# SparkFun_RTK_Facet_-_Main.net
KiCad netlist of a schematic drawn in EAGLE
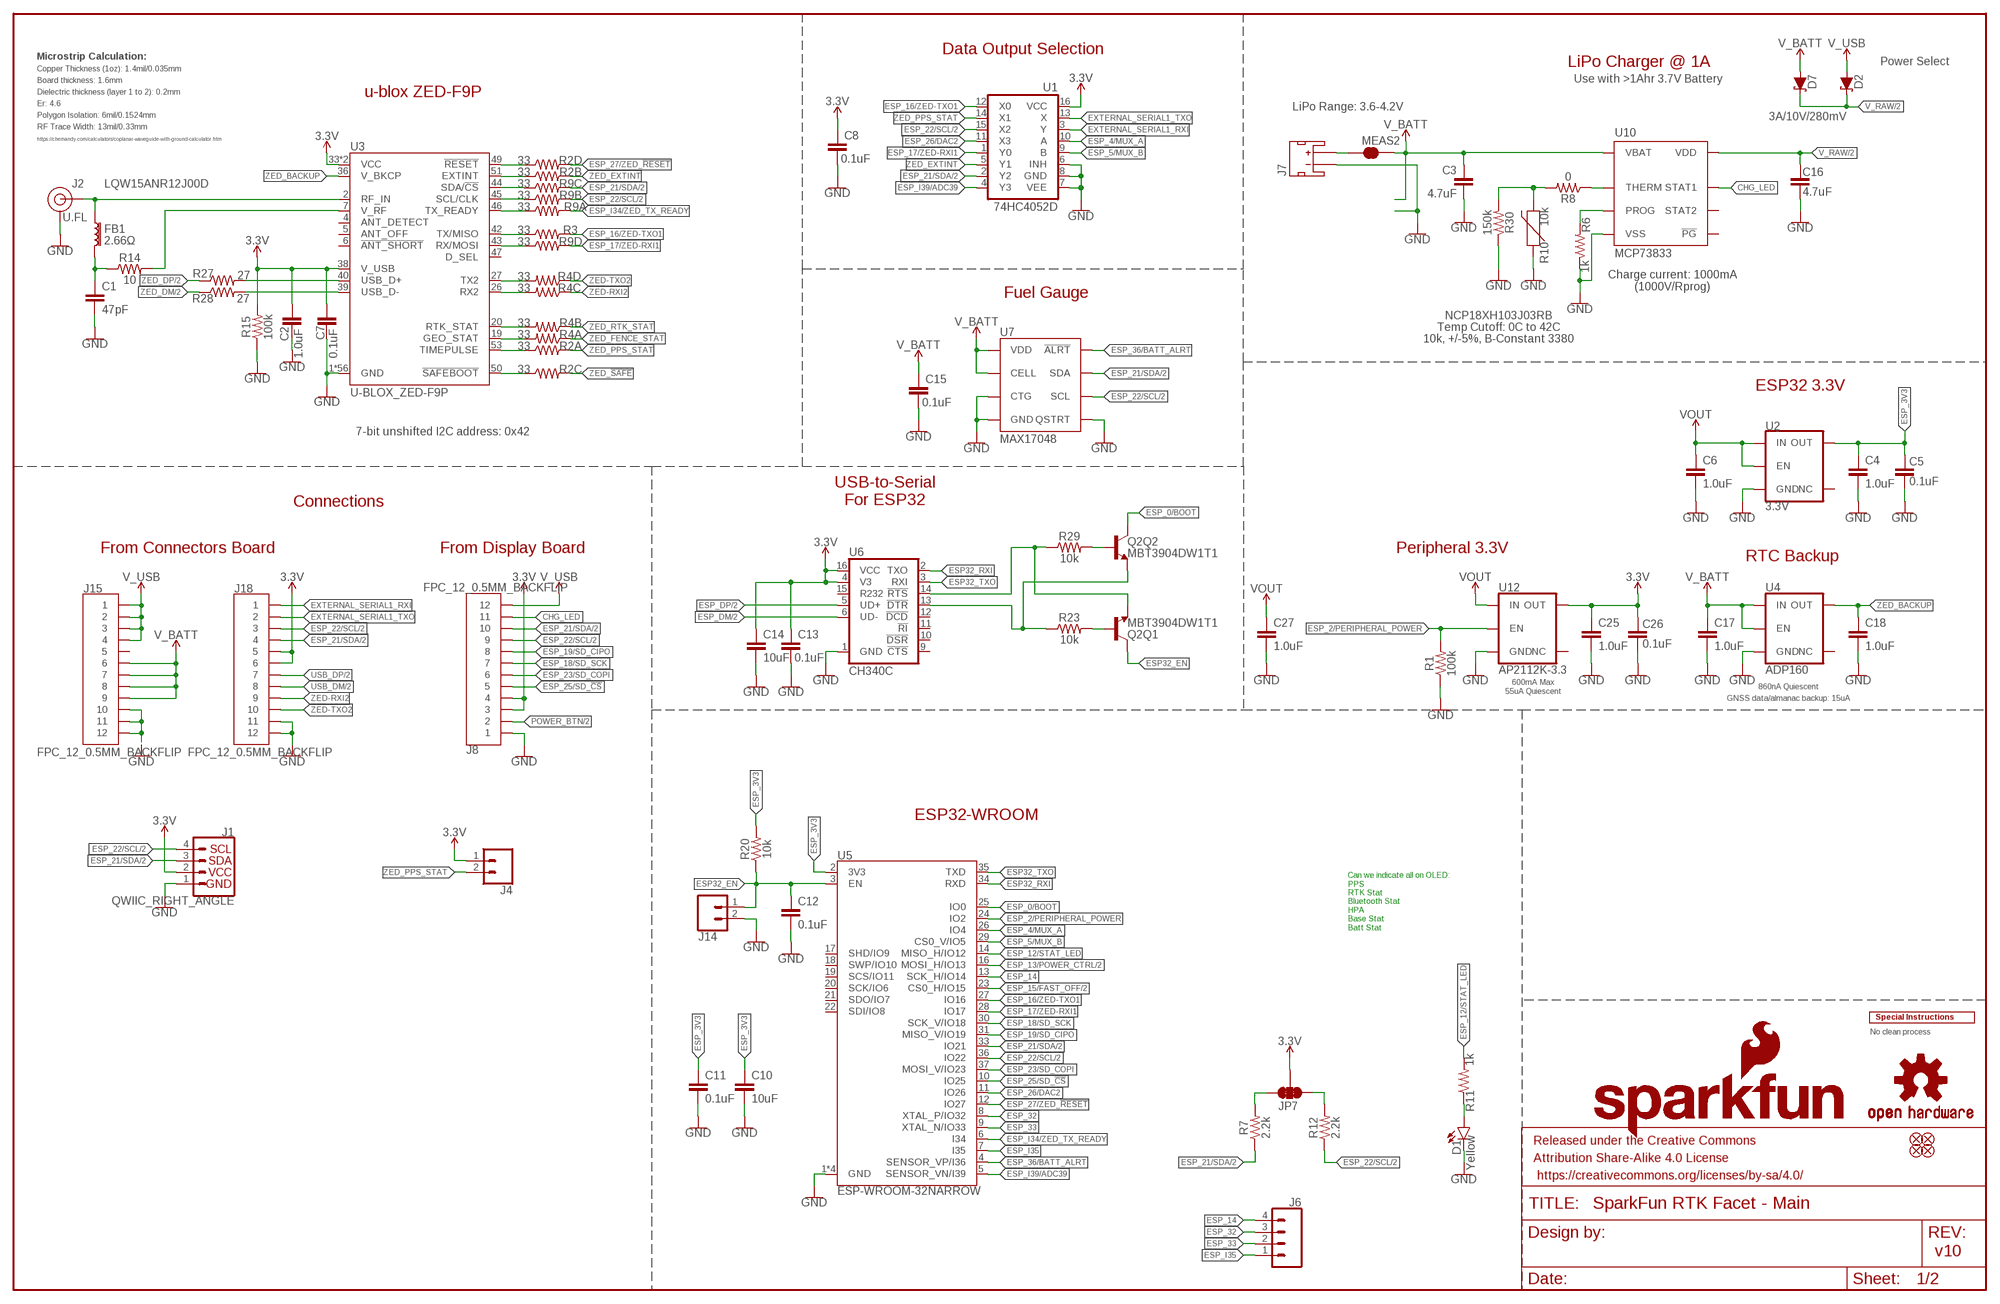
[diagram p0: schematic, sheet 1]
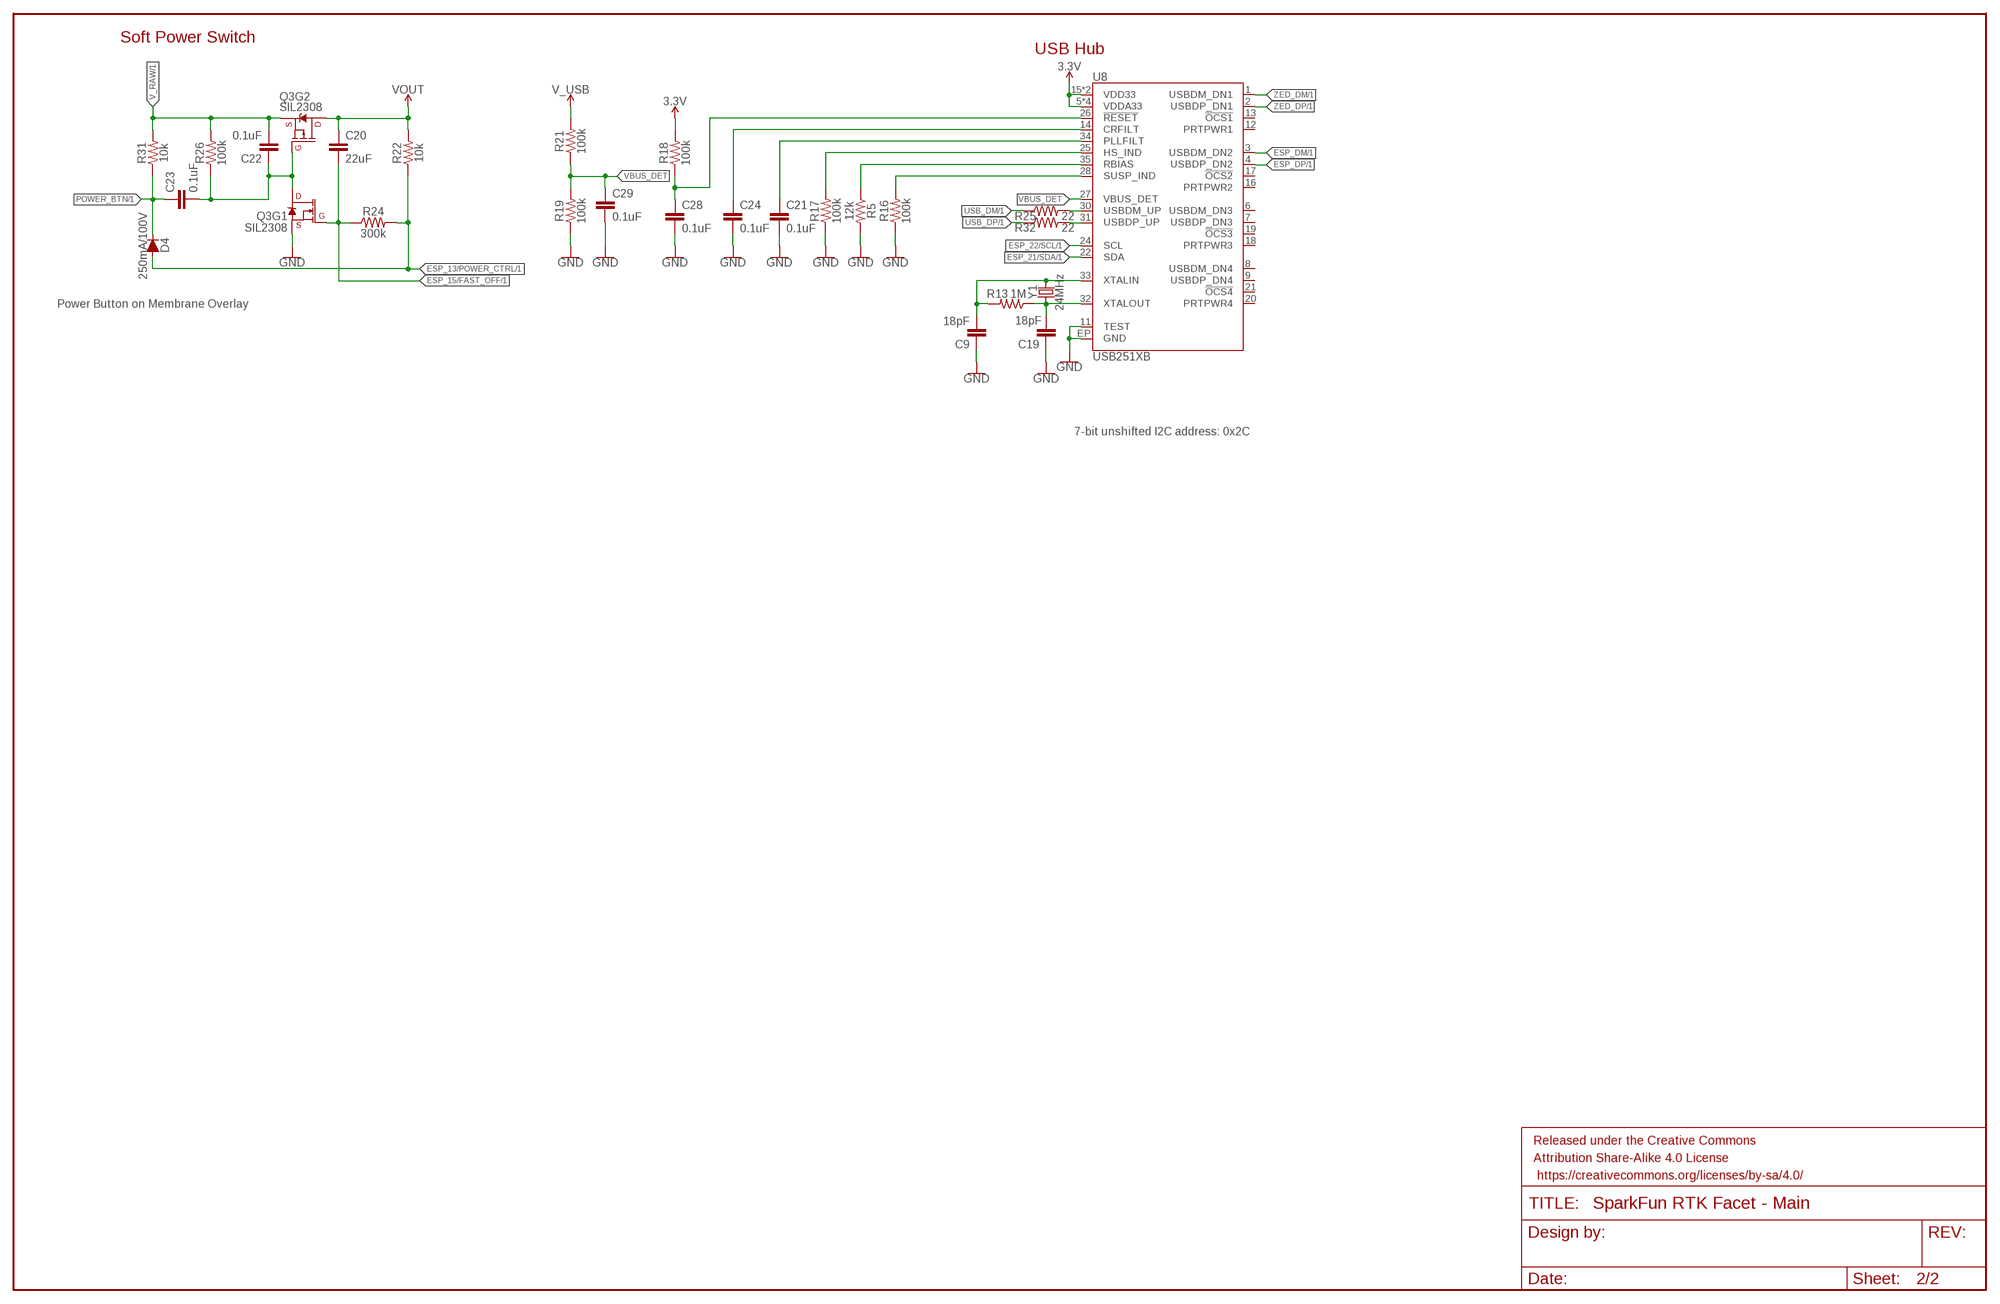
[diagram p1: schematic, sheet 2]

(export (version "E")
  (design (tool "Eeschema 10.0.6"))
  (components
    (comp (ref "C1")
      (value "47pF")
      (footprint "eagle-import:0402")
      (libsource (lib "eagle-import") (part "47PF-0402-25V-5%-X7R"))
    )
    (comp (ref "C2")
      (value "1.0uF")
      (footprint "eagle-import:0603")
      (libsource (lib "eagle-import") (part "1.0UF-0603-16V-10%-X7R"))
    )
    (comp (ref "C3")
      (value "4.7uF")
      (footprint "eagle-import:0603")
      (libsource (lib "eagle-import") (part "4.7UF-0603-35V-(20%)"))
    )
    (comp (ref "C4")
      (value "1.0uF")
      (footprint "eagle-import:0603")
      (libsource (lib "eagle-import") (part "1.0UF-0603-16V-10%-X7R"))
    )
    (comp (ref "C5")
      (value "0.1uF")
      (footprint "eagle-import:0603")
      (libsource (lib "eagle-import") (part "0.1UF-0603-25V-5%"))
    )
    (comp (ref "C6")
      (value "1.0uF")
      (footprint "eagle-import:0603")
      (libsource (lib "eagle-import") (part "1.0UF-0603-16V-10%-X7R"))
    )
    (comp (ref "C7")
      (value "0.1uF")
      (footprint "eagle-import:0603")
      (libsource (lib "eagle-import") (part "0.1UF-0603-25V-5%"))
    )
    (comp (ref "C8")
      (value "0.1uF")
      (footprint "eagle-import:0603")
      (libsource (lib "eagle-import") (part "0.1UF-0603-25V-(+80/-20%)"))
    )
    (comp (ref "C10")
      (value "10uF")
      (footprint "eagle-import:0603")
      (libsource (lib "eagle-import") (part "10UF-0603-6.3V-20%"))
    )
    (comp (ref "C11")
      (value "0.1uF")
      (footprint "eagle-import:0603")
      (libsource (lib "eagle-import") (part "0.1UF-0603-25V-(+80/-20%)"))
    )
    (comp (ref "C12")
      (value "0.1uF")
      (footprint "eagle-import:0603")
      (libsource (lib "eagle-import") (part "0.1UF-0603-25V-(+80/-20%)"))
    )
    (comp (ref "C13")
      (value "0.1uF")
      (footprint "eagle-import:0603")
      (libsource (lib "eagle-import") (part "0.1UF-0603-25V-(+80/-20%)"))
    )
    (comp (ref "C14")
      (value "10uF")
      (footprint "eagle-import:0603")
      (libsource (lib "eagle-import") (part "10UF-0603-6.3V-20%"))
    )
    (comp (ref "C15")
      (value "0.1uF")
      (footprint "eagle-import:0603")
      (libsource (lib "eagle-import") (part "0.1UF-0603-25V-(+80/-20%)"))
    )
    (comp (ref "C16")
      (value "4.7uF")
      (footprint "eagle-import:0603")
      (libsource (lib "eagle-import") (part "4.7UF-0603-35V-(20%)"))
    )
    (comp (ref "C17")
      (value "1.0uF")
      (footprint "eagle-import:0603")
      (libsource (lib "eagle-import") (part "1.0UF-0603-16V-10%-X7R"))
    )
    (comp (ref "C18")
      (value "1.0uF")
      (footprint "eagle-import:0603")
      (libsource (lib "eagle-import") (part "1.0UF-0603-16V-10%-X7R"))
    )
    (comp (ref "C25")
      (value "1.0uF")
      (footprint "eagle-import:0603")
      (libsource (lib "eagle-import") (part "1.0UF-0603-16V-10%-X7R"))
    )
    (comp (ref "C26")
      (value "0.1uF")
      (footprint "eagle-import:0603")
      (libsource (lib "eagle-import") (part "0.1UF-0603-25V-5%"))
    )
    (comp (ref "C27")
      (value "1.0uF")
      (footprint "eagle-import:0603")
      (libsource (lib "eagle-import") (part "1.0UF-0603-16V-10%-X7R"))
    )
    (comp (ref "D1")
      (value "Yellow")
      (footprint "eagle-import:LED-0603")
      (libsource (lib "eagle-import") (part "LED-YELLOW0603"))
    )
    (comp (ref "D2")
      (value "3A/10V/280mV")
      (footprint "eagle-import:SOD-323")
      (libsource (lib "eagle-import") (part "DIODE-SCHOTTKY-BAT60A"))
    )
    (comp (ref "D7")
      (value "3A/10V/280mV")
      (footprint "eagle-import:SOD-323")
      (libsource (lib "eagle-import") (part "DIODE-SCHOTTKY-BAT60A"))
    )
    (comp (ref "FB1")
      (value "2.66Ω")
      (footprint "eagle-import:0402-TIGHT")
      (libsource (lib "eagle-import") (part "FERRITE_BEAD-0402-2.66OHM-1GHZ"))
    )
    (comp (ref "FRAME2")
      (value "FRAME-LEDGER")
      (footprint "eagle-import:CREATIVE_COMMONS")
      (libsource (lib "eagle-import") (part "FRAME-LEDGER"))
    )
    (comp (ref "J1")
      (value "QWIIC_RIGHT_ANGLE")
      (footprint "eagle-import:JST04_1MM_RA")
      (libsource (lib "eagle-import") (part "QWIIC_CONNECTORJS-1MM"))
    )
    (comp (ref "J2")
      (value "U.FL")
      (footprint "eagle-import:U.FL")
      (libsource (lib "eagle-import") (part "U.FL2PIN"))
    )
    (comp (ref "J4")
      (value "CONN_021X02_NO_SILK")
      (footprint "eagle-import:1X02_NO_SILK")
      (libsource (lib "eagle-import") (part "CONN_021X02_NO_SILK"))
    )
    (comp (ref "J6")
      (value "CONN_041X04_NO_SILK_NO_POP")
      (footprint "eagle-import:1X04_NO_SILK")
      (libsource (lib "eagle-import") (part "CONN_041X04_NO_SILK_NO_POP"))
    )
    (comp (ref "J7")
      (value "JST_2MM_MALE")
      (footprint "eagle-import:JST-2-SMD")
      (libsource (lib "eagle-import") (part "JST_2MM_MALE"))
    )
    (comp (ref "J8")
      (value "FPC_12_0.5MM_BACKFLIP")
      (footprint "eagle-import:FPC_12_DOUBLESIDED_BACKFLIP")
      (libsource (lib "eagle-import") (part "FPC_12_0.5MM_BACKFLIP"))
    )
    (comp (ref "J14")
      (value "CONN_021X02_NO_SILK")
      (footprint "eagle-import:1X02_NO_SILK")
      (libsource (lib "eagle-import") (part "CONN_021X02_NO_SILK"))
    )
    (comp (ref "J15")
      (value "FPC_12_0.5MM_BACKFLIP")
      (footprint "eagle-import:FPC_12_DOUBLESIDED_BACKFLIP")
      (libsource (lib "eagle-import") (part "FPC_12_0.5MM_BACKFLIP"))
    )
    (comp (ref "J18")
      (value "FPC_12_0.5MM_BACKFLIP")
      (footprint "eagle-import:FPC_12_DOUBLESIDED_BACKFLIP")
      (libsource (lib "eagle-import") (part "FPC_12_0.5MM_BACKFLIP"))
    )
    (comp (ref "JP7")
      (value "JUMPER-SMT_3_2-NC_TRACE_SILK")
      (footprint "eagle-import:SMT-JUMPER_3_2-NC_TRACE_SILK")
      (libsource (lib "eagle-import") (part "JUMPER-SMT_3_2-NC_TRACE_SILK"))
    )
    (comp (ref "JP21")
      (value "FIDUCIALUFIDUCIAL")
      (footprint "eagle-import:FIDUCIAL-MICRO")
      (libsource (lib "eagle-import") (part "FIDUCIALUFIDUCIAL"))
    )
    (comp (ref "JP61")
      (value "FIDUCIALUFIDUCIAL")
      (footprint "eagle-import:FIDUCIAL-MICRO")
      (libsource (lib "eagle-import") (part "FIDUCIALUFIDUCIAL"))
    )
    (comp (ref "JP71")
      (value "FIDUCIALUFIDUCIAL")
      (footprint "eagle-import:FIDUCIAL-MICRO")
      (libsource (lib "eagle-import") (part "FIDUCIALUFIDUCIAL"))
    )
    (comp (ref "JP81")
      (value "FIDUCIALUFIDUCIAL")
      (footprint "eagle-import:FIDUCIAL-MICRO")
      (libsource (lib "eagle-import") (part "FIDUCIALUFIDUCIAL"))
    )
    (comp (ref "LOGO1")
      (value "OSHW-LOGOMINI")
      (footprint "eagle-import:OSHW-LOGO-MINI")
      (libsource (lib "eagle-import") (part "OSHW-LOGOMINI"))
    )
    (comp (ref "LOGO2")
      (value "SFE_LOGO_NAME_FLAME.1_INCH")
      (footprint "eagle-import:SFE_LOGO_NAME_FLAME_.1")
      (libsource (lib "eagle-import") (part "SFE_LOGO_NAME_FLAME.1_INCH"))
    )
    (comp (ref "MEAS2")
      (value "JUMPER-COMBO_2_NC_TRACE")
      (footprint "eagle-import:COMBO-JUMPER_2_NC_TRACE")
      (libsource (lib "eagle-import") (part "JUMPER-COMBO_2_NC_TRACE"))
    )
    (comp (ref "Q2")
      (value "MBT3904DW1T1")
      (footprint "eagle-import:SC70-6")
      (libsource (lib "eagle-import") (part "TRANS_NPN_DUAL-MBT3904DW1T1"))
    )
    (comp (ref "R1")
      (value "100k")
      (footprint "eagle-import:0603")
      (libsource (lib "eagle-import") (part "100KOHM-0603-1/10W-1%"))
    )
    (comp (ref "R2")
      (value "33")
      (footprint "eagle-import:1206_RA")
      (libsource (lib "eagle-import") (part "33OHM_RA-1206-1/16W-5%"))
    )
    (comp (ref "R3")
      (value "33")
      (footprint "eagle-import:0603")
      (libsource (lib "eagle-import") (part "33OHM-0603-1/10W-1%"))
    )
    (comp (ref "R4")
      (value "33")
      (footprint "eagle-import:1206_RA")
      (libsource (lib "eagle-import") (part "33OHM_RA-1206-1/16W-5%"))
    )
    (comp (ref "R6")
      (value "1k")
      (footprint "eagle-import:0603")
      (libsource (lib "eagle-import") (part "1KOHM-0603-1/10W-1%"))
    )
    (comp (ref "R7")
      (value "2.2k")
      (footprint "eagle-import:0603")
      (libsource (lib "eagle-import") (part "2.2KOHM-0603-1/10W-1%"))
    )
    (comp (ref "R8")
      (value "0")
      (footprint "eagle-import:0603")
      (libsource (lib "eagle-import") (part "0OHM-0603-1/10W"))
    )
    (comp (ref "R9")
      (value "33")
      (footprint "eagle-import:1206_RA")
      (libsource (lib "eagle-import") (part "33OHM_RA-1206-1/16W-5%"))
    )
    (comp (ref "R10")
      (value "10k")
      (footprint "eagle-import:0603")
      (libsource (lib "eagle-import") (part "NTC-THERMISTOR-0603"))
    )
    (comp (ref "R11")
      (value "1k")
      (footprint "eagle-import:0603")
      (libsource (lib "eagle-import") (part "1KOHM-0603-1/10W-1%"))
    )
    (comp (ref "R12")
      (value "2.2k")
      (footprint "eagle-import:0603")
      (libsource (lib "eagle-import") (part "2.2KOHM-0603-1/10W-1%"))
    )
    (comp (ref "R14")
      (value "10")
      (footprint "eagle-import:0603")
      (libsource (lib "eagle-import") (part "10OHM-0603-1/10W-1%"))
    )
    (comp (ref "R15")
      (value "100k")
      (footprint "eagle-import:0603")
      (libsource (lib "eagle-import") (part "100KOHM-0603-1/10W-1%"))
    )
    (comp (ref "R20")
      (value "10k")
      (footprint "eagle-import:0603")
      (libsource (lib "eagle-import") (part "10KOHM-0603-1/10W-1%"))
    )
    (comp (ref "R23")
      (value "10k")
      (footprint "eagle-import:0603")
      (libsource (lib "eagle-import") (part "10KOHM-0603-1/10W-1%"))
    )
    (comp (ref "R27")
      (value "27")
      (footprint "eagle-import:0603")
      (libsource (lib "eagle-import") (part "27OHM-0603-1/10W-1%"))
    )
    (comp (ref "R28")
      (value "27")
      (footprint "eagle-import:0603")
      (libsource (lib "eagle-import") (part "27OHM-0603-1/10W-1%"))
    )
    (comp (ref "R29")
      (value "10k")
      (footprint "eagle-import:0603")
      (libsource (lib "eagle-import") (part "10KOHM-0603-1/10W-1%"))
    )
    (comp (ref "R30")
      (value "150k")
      (footprint "eagle-import:0603")
      (libsource (lib "eagle-import") (part "150KOHM-0603-1/10W-1%"))
    )
    (comp (ref "U$2")
      (value "SPECIAL_INSTRUCTIONS-ORDERING")
      (footprint "eagle-import:ORDERING_INSTRUCTIONS")
      (libsource (lib "eagle-import") (part "SPECIAL_INSTRUCTIONS-ORDERING"))
    )
    (comp (ref "U1")
      (value "74HC4052D")
      (footprint "eagle-import:SO16")
      (libsource (lib "eagle-import") (part "744052DHC"))
    )
    (comp (ref "U2")
      (value "3.3V")
      (footprint "eagle-import:SOT23-5")
      (libsource (lib "eagle-import") (part "V_REG_AP2112K-3.3V"))
    )
    (comp (ref "U3")
      (value "U-BLOX_ZED-F9P")
      (footprint "eagle-import:ZED-F9P")
      (libsource (lib "eagle-import") (part "U-BLOX_ZED-F9P"))
    )
    (comp (ref "U4")
      (value "ADP160")
      (footprint "eagle-import:SOT23-5")
      (libsource (lib "eagle-import") (part "ADP160"))
    )
    (comp (ref "U5")
      (value "ESP-WROOM-32NARROW")
      (footprint "eagle-import:ESP-WROOM-32-NARROW")
      (libsource (lib "eagle-import") (part "ESP-WROOM-32NARROW"))
    )
    (comp (ref "U6")
      (value "CH340C")
      (footprint "eagle-import:SO016")
      (libsource (lib "eagle-import") (part "CH340C"))
    )
    (comp (ref "U7")
      (value "MAX17048")
      (footprint "eagle-import:DFN-8")
      (libsource (lib "eagle-import") (part "MAX17048DFN8"))
    )
    (comp (ref "U10")
      (value "MCP73833")
      (footprint "eagle-import:DFN-10")
      (libsource (lib "eagle-import") (part "MCP73833"))
    )
    (comp (ref "U12")
      (value "AP2112K-3.3")
      (footprint "eagle-import:SOT23-5")
      (libsource (lib "eagle-import") (part "V_REG_AP2112K-3.3V"))
    )
    (comp (ref "C9")
      (value "18pF")
      (footprint "eagle-import:0603")
      (libsource (lib "eagle-import") (part "18PF-0603-50V-5%"))
    )
    (comp (ref "C19")
      (value "18pF")
      (footprint "eagle-import:0603")
      (libsource (lib "eagle-import") (part "18PF-0603-50V-5%"))
    )
    (comp (ref "C20")
      (value "22uF")
      (footprint "eagle-import:0603")
      (libsource (lib "eagle-import") (part "22UF-0603-6.3V-20%"))
    )
    (comp (ref "C21")
      (value "0.1uF")
      (footprint "eagle-import:0603")
      (libsource (lib "eagle-import") (part "0.1UF-0603-25V-5%"))
    )
    (comp (ref "C22")
      (value "0.1uF")
      (footprint "eagle-import:0603")
      (libsource (lib "eagle-import") (part "0.1UF-0603-25V-5%"))
    )
    (comp (ref "C23")
      (value "0.1uF")
      (footprint "eagle-import:0603")
      (libsource (lib "eagle-import") (part "0.1UF-0603-25V-5%"))
    )
    (comp (ref "C24")
      (value "0.1uF")
      (footprint "eagle-import:0603")
      (libsource (lib "eagle-import") (part "0.1UF-0603-25V-5%"))
    )
    (comp (ref "C28")
      (value "0.1uF")
      (footprint "eagle-import:0603")
      (libsource (lib "eagle-import") (part "0.1UF-0603-25V-5%"))
    )
    (comp (ref "C29")
      (value "0.1uF")
      (footprint "eagle-import:0603")
      (libsource (lib "eagle-import") (part "0.1UF-0603-25V-5%"))
    )
    (comp (ref "D4")
      (value "250mA/100V")
      (footprint "eagle-import:SOD-323")
      (libsource (lib "eagle-import") (part "DIODE-BAS16J"))
    )
    (comp (ref "FRAME1")
      (value "FRAME-LEDGER")
      (footprint "eagle-import:CREATIVE_COMMONS")
      (libsource (lib "eagle-import") (part "FRAME-LEDGER"))
    )
    (comp (ref "Q3")
      (value "SIL2308")
      (footprint "eagle-import:SOT26")
      (libsource (lib "eagle-import") (part "MOSFET_COMPLIMENTARY_PAIR-SIL2308"))
    )
    (comp (ref "R5")
      (value "12k")
      (footprint "eagle-import:0603")
      (libsource (lib "eagle-import") (part "12KOHM-0603-1/10W-1%"))
    )
    (comp (ref "R13")
      (value "1M")
      (footprint "eagle-import:0603")
      (libsource (lib "eagle-import") (part "1MOHM-0603-1/4W-5%"))
    )
    (comp (ref "R16")
      (value "100k")
      (footprint "eagle-import:0603")
      (libsource (lib "eagle-import") (part "100KOHM-0603-1/10W-1%"))
    )
    (comp (ref "R17")
      (value "100k")
      (footprint "eagle-import:0603")
      (libsource (lib "eagle-import") (part "100KOHM-0603-1/10W-1%"))
    )
    (comp (ref "R18")
      (value "100k")
      (footprint "eagle-import:0603")
      (libsource (lib "eagle-import") (part "100KOHM-0603-1/10W-1%"))
    )
    (comp (ref "R19")
      (value "100k")
      (footprint "eagle-import:0603")
      (libsource (lib "eagle-import") (part "100KOHM-0603-1/10W-1%"))
    )
    (comp (ref "R21")
      (value "100k")
      (footprint "eagle-import:0603")
      (libsource (lib "eagle-import") (part "100KOHM-0603-1/10W-1%"))
    )
    (comp (ref "R22")
      (value "10k")
      (footprint "eagle-import:0603")
      (libsource (lib "eagle-import") (part "10KOHM-0603-1/10W-1%"))
    )
    (comp (ref "R24")
      (value "300k")
      (footprint "eagle-import:0603")
      (libsource (lib "eagle-import") (part "300KOHM-0603-1/10W-1%"))
    )
    (comp (ref "R25")
      (value "22")
      (footprint "eagle-import:0603")
      (libsource (lib "eagle-import") (part "22OHM-0603-1/10W-1%"))
    )
    (comp (ref "R26")
      (value "100k")
      (footprint "eagle-import:0603")
      (libsource (lib "eagle-import") (part "100KOHM-0603-1/10W-1%"))
    )
    (comp (ref "R31")
      (value "10k")
      (footprint "eagle-import:0603")
      (libsource (lib "eagle-import") (part "10KOHM-0603-1/10W-1%"))
    )
    (comp (ref "R32")
      (value "22")
      (footprint "eagle-import:0603")
      (libsource (lib "eagle-import") (part "22OHM-0603-1/10W-1%"))
    )
    (comp (ref "U8")
      (value "USB251XB")
      (footprint "eagle-import:QFN-36")
      (libsource (lib "eagle-import") (part "USB251XB"))
    )
    (comp (ref "Y1")
      (value "24MHz")
      (footprint "eagle-import:CRYSTAL-SMD-2.0X1.6MM")
      (libsource (lib "eagle-import") (part "CRYSTAL-24MHZ-SMD-2.0X1.6MM"))
    )
  )
  (nets
    (net (code "1") (name "3.3V") (class "Default")
      (node (ref "C13") (pin "1") (pinfunction "1_1") (pintype "passive"))
      (node (ref "C14") (pin "1") (pinfunction "1_1") (pintype "passive"))
      (node (ref "C2") (pin "1") (pinfunction "1_1") (pintype "passive"))
      (node (ref "C25") (pin "1") (pinfunction "1_1") (pintype "passive"))
      (node (ref "C26") (pin "2") (pinfunction "2_2") (pintype "passive"))
      (node (ref "C7") (pin "2") (pinfunction "2_2") (pintype "passive"))
      (node (ref "C8") (pin "1") (pinfunction "1_1") (pintype "passive"))
      (node (ref "J1") (pin "2") (pinfunction "2_2") (pintype "power_in"))
      (node (ref "J18") (pin "5") (pinfunction "5_5") (pintype "bidirectional"))
      (node (ref "J18") (pin "6") (pinfunction "6_6") (pintype "bidirectional"))
      (node (ref "J4") (pin "1") (pinfunction "1_1") (pintype "passive"))
      (node (ref "J8") (pin "3") (pinfunction "3_3") (pintype "bidirectional"))
      (node (ref "J8") (pin "4") (pinfunction "4_4") (pintype "bidirectional"))
      (node (ref "JP7") (pin "2") (pinfunction "2_2") (pintype "passive"))
      (node (ref "R15") (pin "2") (pinfunction "2_2") (pintype "passive"))
      (node (ref "R18") (pin "2") (pinfunction "2_2") (pintype "passive"))
      (node (ref "U1") (pin "16") (pinfunction "VCC_16") (pintype "power_in"))
      (node (ref "U12") (pin "5") (pinfunction "OUT_5") (pintype "passive"))
      (node (ref "U3") (pin "33") (pinfunction "VCC_33") (pintype "bidirectional"))
      (node (ref "U3") (pin "34") (pinfunction "VCC_34") (pintype "bidirectional"))
      (node (ref "U3") (pin "38") (pinfunction "V_USB_38") (pintype "bidirectional"))
      (node (ref "U6") (pin "16") (pinfunction "VCC_16") (pintype "bidirectional"))
      (node (ref "U6") (pin "4") (pinfunction "V3_4") (pintype "bidirectional"))
      (node (ref "U8") (pin "10") (pinfunction "VDDA33_10") (pintype "bidirectional"))
      (node (ref "U8") (pin "15") (pinfunction "VDD33_15") (pintype "bidirectional"))
      (node (ref "U8") (pin "23") (pinfunction "VDD33_23") (pintype "bidirectional"))
      (node (ref "U8") (pin "29") (pinfunction "VDDA33_29") (pintype "bidirectional"))
      (node (ref "U8") (pin "36") (pinfunction "VDDA33_36") (pintype "bidirectional"))
      (node (ref "U8") (pin "5") (pinfunction "VDDA33_5") (pintype "bidirectional"))
    )
    (net (code "2") (name "CHG_LED") (class "Default")
      (node (ref "J8") (pin "11") (pinfunction "11_11") (pintype "bidirectional"))
      (node (ref "U10") (pin "3") (pinfunction "STAT1_3") (pintype "bidirectional"))
    )
    (net (code "3") (name "ESP32_EN") (class "Default")
      (node (ref "C12") (pin "1") (pinfunction "1_1") (pintype "passive"))
      (node (ref "J14") (pin "1") (pinfunction "1_1") (pintype "passive"))
      (node (ref "Q2") (pin "3") (pinfunction "C_3") (pintype "passive"))
      (node (ref "R20") (pin "1") (pinfunction "1_1") (pintype "passive"))
      (node (ref "U5") (pin "3") (pinfunction "EN_3") (pintype "bidirectional"))
    )
    (net (code "4") (name "ESP32_RXI") (class "Default")
      (node (ref "U5") (pin "34") (pinfunction "RXD_34") (pintype "bidirectional"))
      (node (ref "U6") (pin "2") (pinfunction "TXO_2") (pintype "bidirectional"))
    )
    (net (code "5") (name "ESP32_TXO") (class "Default")
      (node (ref "U5") (pin "35") (pinfunction "TXD_35") (pintype "bidirectional"))
      (node (ref "U6") (pin "3") (pinfunction "RXI_3") (pintype "bidirectional"))
    )
    (net (code "6") (name "ESP_0{slash}BOOT") (class "Default")
      (node (ref "Q2") (pin "6") (pinfunction "C_6") (pintype "passive"))
      (node (ref "U5") (pin "25") (pinfunction "IO0_25") (pintype "bidirectional"))
    )
    (net (code "7") (name "ESP_2{slash}PERIPHERAL_POWER") (class "Default")
      (node (ref "R1") (pin "2") (pinfunction "2_2") (pintype "passive"))
      (node (ref "U12") (pin "3") (pinfunction "EN_3") (pintype "input"))
      (node (ref "U5") (pin "24") (pinfunction "IO2_24") (pintype "bidirectional"))
    )
    (net (code "8") (name "ESP_3V3") (class "Default")
      (node (ref "C10") (pin "1") (pinfunction "1_1") (pintype "passive"))
      (node (ref "C11") (pin "1") (pinfunction "1_1") (pintype "passive"))
      (node (ref "C4") (pin "1") (pinfunction "1_1") (pintype "passive"))
      (node (ref "C5") (pin "2") (pinfunction "2_2") (pintype "passive"))
      (node (ref "R20") (pin "2") (pinfunction "2_2") (pintype "passive"))
      (node (ref "U2") (pin "5") (pinfunction "OUT_5") (pintype "passive"))
      (node (ref "U5") (pin "2") (pinfunction "3V3_2") (pintype "bidirectional"))
    )
    (net (code "9") (name "ESP_4{slash}MUX_A") (class "Default")
      (node (ref "U1") (pin "10") (pinfunction "A_10") (pintype "input"))
      (node (ref "U5") (pin "26") (pinfunction "IO4_26") (pintype "bidirectional"))
    )
    (net (code "10") (name "ESP_5{slash}MUX_B") (class "Default")
      (node (ref "U1") (pin "9") (pinfunction "B_9") (pintype "input"))
      (node (ref "U5") (pin "29") (pinfunction "CS0_V/IO5_29") (pintype "bidirectional"))
    )
    (net (code "11") (name "ESP_12{slash}STAT_LED") (class "Default")
      (node (ref "R11") (pin "2") (pinfunction "2_2") (pintype "passive"))
      (node (ref "U5") (pin "14") (pinfunction "MISO_H/IO12_14") (pintype "bidirectional"))
    )
    (net (code "12") (name "ESP_13{slash}POWER_CTRL") (class "Default")
      (node (ref "D4") (pin "A") (pinfunction "A_A") (pintype "passive"))
      (node (ref "R22") (pin "1") (pinfunction "1_1") (pintype "passive"))
      (node (ref "R24") (pin "2") (pinfunction "2_2") (pintype "passive"))
      (node (ref "U5") (pin "16") (pinfunction "MOSI_H/IO13_16") (pintype "bidirectional"))
    )
    (net (code "13") (name "ESP_14") (class "Default")
      (node (ref "J6") (pin "4") (pinfunction "4_4") (pintype "passive"))
      (node (ref "U5") (pin "13") (pinfunction "SCK_H/IO14_13") (pintype "bidirectional"))
    )
    (net (code "14") (name "ESP_15{slash}FAST_OFF") (class "Default")
      (node (ref "C20") (pin "2") (pinfunction "2_2") (pintype "passive"))
      (node (ref "Q3") (pin "G1") (pinfunction "G_G1") (pintype "bidirectional"))
      (node (ref "R24") (pin "1") (pinfunction "1_1") (pintype "passive"))
      (node (ref "U5") (pin "23") (pinfunction "CS0_H/IO15_23") (pintype "bidirectional"))
    )
    (net (code "15") (name "ESP_16{slash}ZED-TXO1") (class "Default")
      (node (ref "R3") (pin "2") (pinfunction "2_2") (pintype "passive"))
      (node (ref "U1") (pin "12") (pinfunction "X0_12") (pintype "bidirectional"))
      (node (ref "U5") (pin "27") (pinfunction "IO16_27") (pintype "bidirectional"))
    )
    (net (code "16") (name "ESP_17{slash}ZED-RXI1") (class "Default")
      (node (ref "R9") (pin "P5") (pinfunction "2_P5") (pintype "passive"))
      (node (ref "U1") (pin "1") (pinfunction "Y0_1") (pintype "bidirectional"))
      (node (ref "U5") (pin "28") (pinfunction "IO17_28") (pintype "bidirectional"))
    )
    (net (code "17") (name "ESP_18{slash}SD_SCK") (class "Default")
      (node (ref "J8") (pin "7") (pinfunction "7_7") (pintype "bidirectional"))
      (node (ref "U5") (pin "30") (pinfunction "SCK_V/IO18_30") (pintype "bidirectional"))
    )
    (net (code "18") (name "ESP_19{slash}SD_CIPO") (class "Default")
      (node (ref "J8") (pin "8") (pinfunction "8_8") (pintype "bidirectional"))
      (node (ref "U5") (pin "31") (pinfunction "MISO_V/IO19_31") (pintype "bidirectional"))
    )
    (net (code "19") (name "ESP_21{slash}SDA") (class "Default")
      (node (ref "J1") (pin "3") (pinfunction "3_3") (pintype "passive"))
      (node (ref "J18") (pin "4") (pinfunction "4_4") (pintype "bidirectional"))
      (node (ref "J8") (pin "10") (pinfunction "10_10") (pintype "bidirectional"))
      (node (ref "R7") (pin "1") (pinfunction "1_1") (pintype "passive"))
      (node (ref "R9") (pin "P6") (pinfunction "2_P6") (pintype "passive"))
      (node (ref "U1") (pin "2") (pinfunction "Y2_2") (pintype "bidirectional"))
      (node (ref "U5") (pin "33") (pinfunction "IO21_33") (pintype "bidirectional"))
      (node (ref "U7") (pin "8") (pinfunction "SDA_8") (pintype "input"))
      (node (ref "U8") (pin "22") (pinfunction "SDA_22") (pintype "bidirectional"))
    )
    (net (code "20") (name "ESP_22{slash}SCL") (class "Default")
      (node (ref "J1") (pin "4") (pinfunction "4_4") (pintype "passive"))
      (node (ref "J18") (pin "3") (pinfunction "3_3") (pintype "bidirectional"))
      (node (ref "J8") (pin "9") (pinfunction "9_9") (pintype "bidirectional"))
      (node (ref "R12") (pin "1") (pinfunction "1_1") (pintype "passive"))
      (node (ref "R9") (pin "P7") (pinfunction "2_P7") (pintype "passive"))
      (node (ref "U1") (pin "15") (pinfunction "X2_15") (pintype "bidirectional"))
      (node (ref "U5") (pin "36") (pinfunction "IO22_36") (pintype "bidirectional"))
      (node (ref "U7") (pin "7") (pinfunction "SCL_7") (pintype "output"))
      (node (ref "U8") (pin "24") (pinfunction "SCL_24") (pintype "bidirectional"))
    )
    (net (code "21") (name "ESP_23{slash}SD_COPI") (class "Default")
      (node (ref "J8") (pin "6") (pinfunction "6_6") (pintype "bidirectional"))
      (node (ref "U5") (pin "37") (pinfunction "MOSI_V/IO23_37") (pintype "bidirectional"))
    )
    (net (code "22") (name "ESP_25{slash}SD_~{CS}") (class "Default")
      (node (ref "J8") (pin "5") (pinfunction "5_5") (pintype "bidirectional"))
      (node (ref "U5") (pin "10") (pinfunction "IO25_10") (pintype "bidirectional"))
    )
    (net (code "23") (name "ESP_26{slash}DAC2") (class "Default")
      (node (ref "U1") (pin "11") (pinfunction "X3_11") (pintype "bidirectional"))
      (node (ref "U5") (pin "11") (pinfunction "IO26_11") (pintype "bidirectional"))
    )
    (net (code "24") (name "ESP_27{slash}ZED_~{RESET}") (class "Default")
      (node (ref "R2") (pin "P5") (pinfunction "2_P5") (pintype "passive"))
      (node (ref "U5") (pin "12") (pinfunction "IO27_12") (pintype "bidirectional"))
    )
    (net (code "25") (name "ESP_32") (class "Default")
      (node (ref "J6") (pin "3") (pinfunction "3_3") (pintype "passive"))
      (node (ref "U5") (pin "8") (pinfunction "XTAL_P/IO32_8") (pintype "bidirectional"))
    )
    (net (code "26") (name "ESP_33") (class "Default")
      (node (ref "J6") (pin "2") (pinfunction "2_2") (pintype "passive"))
      (node (ref "U5") (pin "9") (pinfunction "XTAL_N/IO33_9") (pintype "bidirectional"))
    )
    (net (code "27") (name "ESP_36{slash}BATT_ALRT") (class "Default")
      (node (ref "U5") (pin "4") (pinfunction "SENSOR_VP/I36_4") (pintype "bidirectional"))
      (node (ref "U7") (pin "5") (pinfunction "~{ALRT}_5") (pintype "bidirectional"))
    )
    (net (code "28") (name "ESP_DM") (class "Default")
      (node (ref "U6") (pin "6") (pinfunction "UD-_6") (pintype "bidirectional"))
      (node (ref "U8") (pin "3") (pinfunction "USBDM_DN2_3") (pintype "bidirectional"))
    )
    (net (code "29") (name "ESP_DP") (class "Default")
      (node (ref "U6") (pin "5") (pinfunction "UD+_5") (pintype "bidirectional"))
      (node (ref "U8") (pin "4") (pinfunction "USBDP_DN2_4") (pintype "bidirectional"))
    )
    (net (code "30") (name "ESP_I34{slash}ZED_TX_READY") (class "Default")
      (node (ref "R9") (pin "P8") (pinfunction "2_P8") (pintype "passive"))
      (node (ref "U5") (pin "6") (pinfunction "I34_6") (pintype "bidirectional"))
    )
    (net (code "31") (name "ESP_I35") (class "Default")
      (node (ref "J6") (pin "1") (pinfunction "1_1") (pintype "passive"))
      (node (ref "U5") (pin "7") (pinfunction "I35_7") (pintype "bidirectional"))
    )
    (net (code "32") (name "ESP_I39{slash}ADC39") (class "Default")
      (node (ref "U1") (pin "4") (pinfunction "Y3_4") (pintype "bidirectional"))
      (node (ref "U5") (pin "5") (pinfunction "SENSOR_VN/I39_5") (pintype "bidirectional"))
    )
    (net (code "33") (name "EXTERNAL_SERIAL1_RXI") (class "Default")
      (node (ref "J18") (pin "1") (pinfunction "1_1") (pintype "bidirectional"))
      (node (ref "U1") (pin "3") (pinfunction "Y_3") (pintype "bidirectional"))
    )
    (net (code "34") (name "EXTERNAL_SERIAL1_TXO") (class "Default")
      (node (ref "J18") (pin "2") (pinfunction "2_2") (pintype "bidirectional"))
      (node (ref "U1") (pin "13") (pinfunction "X_13") (pintype "bidirectional"))
    )
    (net (code "35") (name "GND") (class "Default")
      (node (ref "C1") (pin "2") (pinfunction "2_2") (pintype "passive"))
      (node (ref "C10") (pin "2") (pinfunction "2_2") (pintype "passive"))
      (node (ref "C11") (pin "2") (pinfunction "2_2") (pintype "passive"))
      (node (ref "C12") (pin "2") (pinfunction "2_2") (pintype "passive"))
      (node (ref "C13") (pin "2") (pinfunction "2_2") (pintype "passive"))
      (node (ref "C14") (pin "2") (pinfunction "2_2") (pintype "passive"))
      (node (ref "C15") (pin "2") (pinfunction "2_2") (pintype "passive"))
      (node (ref "C16") (pin "2") (pinfunction "2_2") (pintype "passive"))
      (node (ref "C17") (pin "2") (pinfunction "2_2") (pintype "passive"))
      (node (ref "C18") (pin "2") (pinfunction "2_2") (pintype "passive"))
      (node (ref "C19") (pin "1") (pinfunction "1_1") (pintype "passive"))
      (node (ref "C2") (pin "2") (pinfunction "2_2") (pintype "passive"))
      (node (ref "C21") (pin "2") (pinfunction "2_2") (pintype "passive"))
      (node (ref "C24") (pin "2") (pinfunction "2_2") (pintype "passive"))
      (node (ref "C25") (pin "2") (pinfunction "2_2") (pintype "passive"))
      (node (ref "C26") (pin "1") (pinfunction "1_1") (pintype "passive"))
      (node (ref "C27") (pin "2") (pinfunction "2_2") (pintype "passive"))
      (node (ref "C28") (pin "2") (pinfunction "2_2") (pintype "passive"))
      (node (ref "C29") (pin "2") (pinfunction "2_2") (pintype "passive"))
      (node (ref "C3") (pin "2") (pinfunction "2_2") (pintype "passive"))
      (node (ref "C4") (pin "2") (pinfunction "2_2") (pintype "passive"))
      (node (ref "C5") (pin "1") (pinfunction "1_1") (pintype "passive"))
      (node (ref "C6") (pin "2") (pinfunction "2_2") (pintype "passive"))
      (node (ref "C7") (pin "1") (pinfunction "1_1") (pintype "passive"))
      (node (ref "C8") (pin "2") (pinfunction "2_2") (pintype "passive"))
      (node (ref "C9") (pin "1") (pinfunction "1_1") (pintype "passive"))
      (node (ref "D1") (pin "C") (pinfunction "C_C") (pintype "passive"))
      (node (ref "J1") (pin "1") (pinfunction "1_1") (pintype "power_in"))
      (node (ref "J14") (pin "2") (pinfunction "2_2") (pintype "passive"))
      (node (ref "J15") (pin "10") (pinfunction "10_10") (pintype "bidirectional"))
      (node (ref "J15") (pin "11") (pinfunction "11_11") (pintype "bidirectional"))
      (node (ref "J15") (pin "12") (pinfunction "12_12") (pintype "bidirectional"))
      (node (ref "J18") (pin "11") (pinfunction "11_11") (pintype "bidirectional"))
      (node (ref "J18") (pin "12") (pinfunction "12_12") (pintype "bidirectional"))
      (node (ref "J2") (pin "1") (pinfunction "GND_1") (pintype "bidirectional"))
      (node (ref "J2") (pin "2") (pinfunction "GND_2") (pintype "bidirectional"))
      (node (ref "J7") (pin "1") (pinfunction "-_1") (pintype "bidirectional"))
      (node (ref "J8") (pin "1") (pinfunction "1_1") (pintype "bidirectional"))
      (node (ref "Q3") (pin "S1") (pinfunction "S_S1") (pintype "bidirectional"))
      (node (ref "R1") (pin "1") (pinfunction "1_1") (pintype "passive"))
      (node (ref "R10") (pin "1") (pinfunction "1_1") (pintype "bidirectional"))
      (node (ref "R15") (pin "1") (pinfunction "1_1") (pintype "passive"))
      (node (ref "R16") (pin "1") (pinfunction "1_1") (pintype "passive"))
      (node (ref "R17") (pin "1") (pinfunction "1_1") (pintype "passive"))
      (node (ref "R19") (pin "1") (pinfunction "1_1") (pintype "passive"))
      (node (ref "R30") (pin "1") (pinfunction "1_1") (pintype "passive"))
      (node (ref "R5") (pin "2") (pinfunction "2_2") (pintype "passive"))
      (node (ref "R6") (pin "1") (pinfunction "1_1") (pintype "passive"))
      (node (ref "U1") (pin "6") (pinfunction "INH_6") (pintype "input"))
      (node (ref "U1") (pin "7") (pinfunction "VEE_7") (pintype "power_in"))
      (node (ref "U1") (pin "8") (pinfunction "GND_8") (pintype "power_in"))
      (node (ref "U10") (pin "11") (pinfunction "VSS_11") (pintype "bidirectional"))
      (node (ref "U10") (pin "5") (pinfunction "VSS_5") (pintype "bidirectional"))
      (node (ref "U12") (pin "2") (pinfunction "GND_2") (pintype "input"))
      (node (ref "U2") (pin "2") (pinfunction "GND_2") (pintype "input"))
      (node (ref "U3") (pin "1") (pinfunction "GND_1") (pintype "bidirectional"))
      (node (ref "U3") (pin "100") (pinfunction "GND_100") (pintype "bidirectional"))
      (node (ref "U3") (pin "101") (pinfunction "GND_101") (pintype "bidirectional"))
      (node (ref "U3") (pin "102") (pinfunction "GND_102") (pintype "bidirectional"))
      (node (ref "U3") (pin "12") (pinfunction "GND_12") (pintype "bidirectional"))
      (node (ref "U3") (pin "14") (pinfunction "GND_14") (pintype "bidirectional"))
      (node (ref "U3") (pin "3") (pinfunction "GND_3") (pintype "bidirectional"))
      (node (ref "U3") (pin "32") (pinfunction "GND_32") (pintype "bidirectional"))
      (node (ref "U3") (pin "37") (pinfunction "GND_37") (pintype "bidirectional"))
      (node (ref "U3") (pin "41") (pinfunction "GND_41") (pintype "bidirectional"))
      (node (ref "U3") (pin "48") (pinfunction "GND_48") (pintype "bidirectional"))
      (node (ref "U3") (pin "55") (pinfunction "GND_55") (pintype "bidirectional"))
      (node (ref "U3") (pin "56") (pinfunction "GND_56") (pintype "bidirectional"))
      (node (ref "U3") (pin "57") (pinfunction "GND_57") (pintype "bidirectional"))
      (node (ref "U3") (pin "58") (pinfunction "GND_58") (pintype "bidirectional"))
      (node (ref "U3") (pin "59") (pinfunction "GND_59") (pintype "bidirectional"))
      (node (ref "U3") (pin "60") (pinfunction "GND_60") (pintype "bidirectional"))
      (node (ref "U3") (pin "61") (pinfunction "GND_61") (pintype "bidirectional"))
      (node (ref "U3") (pin "62") (pinfunction "GND_62") (pintype "bidirectional"))
      (node (ref "U3") (pin "63") (pinfunction "GND_63") (pintype "bidirectional"))
      (node (ref "U3") (pin "64") (pinfunction "GND_64") (pintype "bidirectional"))
      (node (ref "U3") (pin "65") (pinfunction "GND_65") (pintype "bidirectional"))
      (node (ref "U3") (pin "66") (pinfunction "GND_66") (pintype "bidirectional"))
      (node (ref "U3") (pin "67") (pinfunction "GND_67") (pintype "bidirectional"))
      (node (ref "U3") (pin "68") (pinfunction "GND_68") (pintype "bidirectional"))
      (node (ref "U3") (pin "69") (pinfunction "GND_69") (pintype "bidirectional"))
      (node (ref "U3") (pin "70") (pinfunction "GND_70") (pintype "bidirectional"))
      (node (ref "U3") (pin "71") (pinfunction "GND_71") (pintype "bidirectional"))
      (node (ref "U3") (pin "72") (pinfunction "GND_72") (pintype "bidirectional"))
      (node (ref "U3") (pin "73") (pinfunction "GND_73") (pintype "bidirectional"))
      (node (ref "U3") (pin "74") (pinfunction "GND_74") (pintype "bidirectional"))
      (node (ref "U3") (pin "75") (pinfunction "GND_75") (pintype "bidirectional"))
      (node (ref "U3") (pin "76") (pinfunction "GND_76") (pintype "bidirectional"))
      (node (ref "U3") (pin "77") (pinfunction "GND_77") (pintype "bidirectional"))
      (node (ref "U3") (pin "78") (pinfunction "GND_78") (pintype "bidirectional"))
      (node (ref "U3") (pin "79") (pinfunction "GND_79") (pintype "bidirectional"))
      (node (ref "U3") (pin "80") (pinfunction "GND_80") (pintype "bidirectional"))
      (node (ref "U3") (pin "81") (pinfunction "GND_81") (pintype "bidirectional"))
      (node (ref "U3") (pin "82") (pinfunction "GND_82") (pintype "bidirectional"))
      (node (ref "U3") (pin "83") (pinfunction "GND_83") (pintype "bidirectional"))
      (node (ref "U3") (pin "84") (pinfunction "GND_84") (pintype "bidirectional"))
      (node (ref "U3") (pin "85") (pinfunction "GND_85") (pintype "bidirectional"))
      (node (ref "U3") (pin "86") (pinfunction "GND_86") (pintype "bidirectional"))
      (node (ref "U3") (pin "87") (pinfunction "GND_87") (pintype "bidirectional"))
      (node (ref "U3") (pin "88") (pinfunction "GND_88") (pintype "bidirectional"))
      (node (ref "U3") (pin "89") (pinfunction "GND_89") (pintype "bidirectional"))
      (node (ref "U3") (pin "90") (pinfunction "GND_90") (pintype "bidirectional"))
      (node (ref "U3") (pin "91") (pinfunction "GND_91") (pintype "bidirectional"))
      (node (ref "U3") (pin "92") (pinfunction "GND_92") (pintype "bidirectional"))
      (node (ref "U3") (pin "93") (pinfunction "GND_93") (pintype "bidirectional"))
      (node (ref "U3") (pin "94") (pinfunction "GND_94") (pintype "bidirectional"))
      (node (ref "U3") (pin "95") (pinfunction "GND_95") (pintype "bidirectional"))
      (node (ref "U3") (pin "96") (pinfunction "GND_96") (pintype "bidirectional"))
      (node (ref "U3") (pin "97") (pinfunction "GND_97") (pintype "bidirectional"))
      (node (ref "U3") (pin "98") (pinfunction "GND_98") (pintype "bidirectional"))
      (node (ref "U3") (pin "99") (pinfunction "GND_99") (pintype "bidirectional"))
      (node (ref "U4") (pin "2") (pinfunction "GND_2") (pintype "input"))
      (node (ref "U5") (pin "1") (pinfunction "GND_1") (pintype "bidirectional"))
      (node (ref "U5") (pin "15") (pinfunction "GND_15") (pintype "bidirectional"))
      (node (ref "U5") (pin "38") (pinfunction "GND_38") (pintype "bidirectional"))
      (node (ref "U5") (pin "GND") (pinfunction "GND_GND") (pintype "bidirectional"))
      (node (ref "U6") (pin "1") (pinfunction "GND_1") (pintype "bidirectional"))
      (node (ref "U7") (pin "1") (pinfunction "CTG_1") (pintype "input"))
      (node (ref "U7") (pin "4") (pinfunction "GND_4") (pintype "bidirectional"))
      (node (ref "U7") (pin "6") (pinfunction "QSTRT_6") (pintype "bidirectional"))
      (node (ref "U7") (pin "9") (pinfunction "GND_9") (pintype "bidirectional"))
      (node (ref "U8") (pin "11") (pinfunction "TEST_11") (pintype "bidirectional"))
      (node (ref "U8") (pin "EP") (pinfunction "GND_EP") (pintype "bidirectional"))
    )
    (net (code "36") (name "Net-(C1-Pad1)") (class "Default")
      (node (ref "C1") (pin "1") (pinfunction "1_1") (pintype "passive"))
      (node (ref "FB1") (pin "2") (pinfunction "2_2") (pintype "passive"))
      (node (ref "R14") (pin "1") (pinfunction "1_1") (pintype "passive"))
    )
    (net (code "37") (name "Net-(D1-PadA)") (class "Default")
      (node (ref "D1") (pin "A") (pinfunction "A_A") (pintype "passive"))
      (node (ref "R11") (pin "1") (pinfunction "1_1") (pintype "passive"))
    )
    (net (code "38") (name "Net-(J2-SIGNAL)") (class "Default")
      (node (ref "FB1") (pin "1") (pinfunction "1_1") (pintype "passive"))
      (node (ref "J2") (pin "FEED") (pinfunction "SIGNAL_FEED") (pintype "bidirectional"))
      (node (ref "U3") (pin "2") (pinfunction "RF_IN_2") (pintype "bidirectional"))
    )
    (net (code "39") (name "Net-(J7-+)") (class "Default")
      (node (ref "J7") (pin "2") (pinfunction "+_2") (pintype "bidirectional"))
      (node (ref "MEAS2") (pin "1") (pinfunction "1_1") (pintype "passive"))
      (node (ref "MEAS2") (pin "3") (pinfunction "1_3") (pintype "passive"))
    )
    (net (code "40") (name "Net-(JP7-Pad1)") (class "Default")
      (node (ref "JP7") (pin "1") (pinfunction "1_1") (pintype "passive"))
      (node (ref "R12") (pin "2") (pinfunction "2_2") (pintype "passive"))
    )
    (net (code "41") (name "Net-(JP7-Pad3)") (class "Default")
      (node (ref "JP7") (pin "3") (pinfunction "3_3") (pintype "passive"))
      (node (ref "R7") (pin "2") (pinfunction "2_2") (pintype "passive"))
    )
    (net (code "42") (name "Net-(Q2A-B)") (class "Default")
      (node (ref "Q2") (pin "5") (pinfunction "B_5") (pintype "passive"))
      (node (ref "R23") (pin "2") (pinfunction "2_2") (pintype "passive"))
    )
    (net (code "43") (name "Net-(Q2A-E)") (class "Default")
      (node (ref "Q2") (pin "4") (pinfunction "E_4") (pintype "passive"))
      (node (ref "R29") (pin "1") (pinfunction "1_1") (pintype "passive"))
      (node (ref "U6") (pin "14") (pinfunction "~{RTS}_14") (pintype "bidirectional"))
    )
    (net (code "44") (name "Net-(Q2B-B)") (class "Default")
      (node (ref "Q2") (pin "2") (pinfunction "B_2") (pintype "passive"))
      (node (ref "R29") (pin "2") (pinfunction "2_2") (pintype "passive"))
    )
    (net (code "45") (name "Net-(Q2B-E)") (class "Default")
      (node (ref "Q2") (pin "1") (pinfunction "E_1") (pintype "passive"))
      (node (ref "R23") (pin "1") (pinfunction "1_1") (pintype "passive"))
      (node (ref "U6") (pin "13") (pinfunction "~{DTR}_13") (pintype "bidirectional"))
    )
    (net (code "46") (name "Net-(Q3A-D)") (class "Default")
      (node (ref "C22") (pin "1") (pinfunction "1_1") (pintype "passive"))
      (node (ref "C23") (pin "2") (pinfunction "2_2") (pintype "passive"))
      (node (ref "Q3") (pin "D1") (pinfunction "D_D1") (pintype "bidirectional"))
      (node (ref "Q3") (pin "G2") (pinfunction "G_G2") (pintype "bidirectional"))
      (node (ref "R26") (pin "1") (pinfunction "1_1") (pintype "passive"))
    )
    (net (code "47") (name "Net-(R2A-1)") (class "Default")
      (node (ref "R2") (pin "P1") (pinfunction "1_P1") (pintype "passive"))
      (node (ref "U3") (pin "53") (pinfunction "TIMEPULSE_53") (pintype "bidirectional"))
    )
    (net (code "48") (name "Net-(R2B-1)") (class "Default")
      (node (ref "R2") (pin "P2") (pinfunction "1_P2") (pintype "passive"))
      (node (ref "U3") (pin "51") (pinfunction "EXTINT_51") (pintype "bidirectional"))
    )
    (net (code "49") (name "Net-(R2C-1)") (class "Default")
      (node (ref "R2") (pin "P3") (pinfunction "1_P3") (pintype "passive"))
      (node (ref "U3") (pin "50") (pinfunction "~{SAFEBOOT}_50") (pintype "bidirectional"))
    )
    (net (code "50") (name "Net-(R2D-1)") (class "Default")
      (node (ref "R2") (pin "P4") (pinfunction "1_P4") (pintype "passive"))
      (node (ref "U3") (pin "49") (pinfunction "~{RESET}_49") (pintype "bidirectional"))
    )
    (net (code "51") (name "Net-(R4A-2)") (class "Default")
      (node (ref "R4") (pin "P8") (pinfunction "2_P8") (pintype "passive"))
      (node (ref "U3") (pin "19") (pinfunction "GEO_STAT_19") (pintype "bidirectional"))
    )
    (net (code "52") (name "Net-(R4B-2)") (class "Default")
      (node (ref "R4") (pin "P7") (pinfunction "2_P7") (pintype "passive"))
      (node (ref "U3") (pin "20") (pinfunction "RTK_STAT_20") (pintype "bidirectional"))
    )
    (net (code "53") (name "Net-(R4C-2)") (class "Default")
      (node (ref "R4") (pin "P6") (pinfunction "2_P6") (pintype "passive"))
      (node (ref "U3") (pin "26") (pinfunction "RX2_26") (pintype "bidirectional"))
    )
    (net (code "54") (name "Net-(R4D-2)") (class "Default")
      (node (ref "R4") (pin "P5") (pinfunction "2_P5") (pintype "passive"))
      (node (ref "U3") (pin "27") (pinfunction "TX2_27") (pintype "bidirectional"))
    )
    (net (code "55") (name "Net-(R9A-1)") (class "Default")
      (node (ref "R9") (pin "P1") (pinfunction "1_P1") (pintype "passive"))
      (node (ref "U3") (pin "46") (pinfunction "TX_READY_46") (pintype "bidirectional"))
    )
    (net (code "56") (name "Net-(R9B-1)") (class "Default")
      (node (ref "R9") (pin "P2") (pinfunction "1_P2") (pintype "passive"))
      (node (ref "U3") (pin "45") (pinfunction "SCL/CLK_45") (pintype "bidirectional"))
    )
    (net (code "57") (name "Net-(R9C-1)") (class "Default")
      (node (ref "R9") (pin "P3") (pinfunction "1_P3") (pintype "passive"))
      (node (ref "U3") (pin "44") (pinfunction "SDA/~{CS}_44") (pintype "bidirectional"))
    )
    (net (code "58") (name "Net-(R9D-1)") (class "Default")
      (node (ref "R9") (pin "P4") (pinfunction "1_P4") (pintype "passive"))
      (node (ref "U3") (pin "43") (pinfunction "RX/MOSI_43") (pintype "bidirectional"))
    )
    (net (code "59") (name "Net-(R10-Pad2)") (class "Default")
      (node (ref "R10") (pin "2") (pinfunction "2_2") (pintype "bidirectional"))
      (node (ref "R30") (pin "2") (pinfunction "2_2") (pintype "passive"))
      (node (ref "R8") (pin "2") (pinfunction "2_2") (pintype "passive"))
    )
    (net (code "60") (name "Net-(U3-TX{slash}MISO)") (class "Default")
      (node (ref "R3") (pin "1") (pinfunction "1_1") (pintype "passive"))
      (node (ref "U3") (pin "42") (pinfunction "TX/MISO_42") (pintype "bidirectional"))
    )
    (net (code "61") (name "Net-(U3-USB_D+)") (class "Default")
      (node (ref "R27") (pin "2") (pinfunction "2_2") (pintype "passive"))
      (node (ref "U3") (pin "40") (pinfunction "USB_D+_40") (pintype "bidirectional"))
    )
    (net (code "62") (name "Net-(U3-USB_D-)") (class "Default")
      (node (ref "R28") (pin "2") (pinfunction "2_2") (pintype "passive"))
      (node (ref "U3") (pin "39") (pinfunction "USB_D-_39") (pintype "bidirectional"))
    )
    (net (code "63") (name "Net-(U3-V_RF)") (class "Default")
      (node (ref "R14") (pin "2") (pinfunction "2_2") (pintype "passive"))
      (node (ref "U3") (pin "7") (pinfunction "V_RF_7") (pintype "bidirectional"))
    )
    (net (code "64") (name "Net-(U8-CRFILT)") (class "Default")
      (node (ref "C24") (pin "1") (pinfunction "1_1") (pintype "passive"))
      (node (ref "U8") (pin "14") (pinfunction "CRFILT_14") (pintype "bidirectional"))
    )
    (net (code "65") (name "Net-(U8-HS_IND)") (class "Default")
      (node (ref "R17") (pin "2") (pinfunction "2_2") (pintype "passive"))
      (node (ref "U8") (pin "25") (pinfunction "HS_IND_25") (pintype "bidirectional"))
    )
    (net (code "66") (name "Net-(U8-PLLFILT)") (class "Default")
      (node (ref "C21") (pin "1") (pinfunction "1_1") (pintype "passive"))
      (node (ref "U8") (pin "34") (pinfunction "PLLFILT_34") (pintype "bidirectional"))
    )
    (net (code "67") (name "Net-(U8-RBIAS)") (class "Default")
      (node (ref "R5") (pin "1") (pinfunction "1_1") (pintype "passive"))
      (node (ref "U8") (pin "35") (pinfunction "RBIAS_35") (pintype "bidirectional"))
    )
    (net (code "68") (name "Net-(U8-SUSP_IND)") (class "Default")
      (node (ref "R16") (pin "2") (pinfunction "2_2") (pintype "passive"))
      (node (ref "U8") (pin "28") (pinfunction "SUSP_IND_28") (pintype "bidirectional"))
    )
    (net (code "69") (name "Net-(U8-USBDM_UP)") (class "Default")
      (node (ref "R25") (pin "2") (pinfunction "2_2") (pintype "passive"))
      (node (ref "U8") (pin "30") (pinfunction "USBDM_UP_30") (pintype "bidirectional"))
    )
    (net (code "70") (name "Net-(U8-USBDP_UP)") (class "Default")
      (node (ref "R32") (pin "2") (pinfunction "2_2") (pintype "passive"))
      (node (ref "U8") (pin "31") (pinfunction "USBDP_UP_31") (pintype "bidirectional"))
    )
    (net (code "71") (name "Net-(U8-XTALIN)") (class "Default")
      (node (ref "C9") (pin "2") (pinfunction "2_2") (pintype "passive"))
      (node (ref "R13") (pin "2") (pinfunction "2_2") (pintype "passive"))
      (node (ref "U8") (pin "33") (pinfunction "XTALIN_33") (pintype "bidirectional"))
      (node (ref "Y1") (pin "3") (pinfunction "2_3") (pintype "passive"))
    )
    (net (code "72") (name "Net-(U8-XTALOUT)") (class "Default")
      (node (ref "C19") (pin "2") (pinfunction "2_2") (pintype "passive"))
      (node (ref "R13") (pin "1") (pinfunction "1_1") (pintype "passive"))
      (node (ref "U8") (pin "32") (pinfunction "XTALOUT_32") (pintype "bidirectional"))
      (node (ref "Y1") (pin "1") (pinfunction "1_1") (pintype "passive"))
    )
    (net (code "73") (name "Net-(U8-~{RESET})") (class "Default")
      (node (ref "C28") (pin "1") (pinfunction "1_1") (pintype "passive"))
      (node (ref "R18") (pin "1") (pinfunction "1_1") (pintype "passive"))
      (node (ref "U8") (pin "26") (pinfunction "~{RESET}_26") (pintype "bidirectional"))
    )
    (net (code "74") (name "Net-(U10-PROG)") (class "Default")
      (node (ref "R6") (pin "2") (pinfunction "2_2") (pintype "passive"))
      (node (ref "U10") (pin "6") (pinfunction "PROG_6") (pintype "bidirectional"))
    )
    (net (code "75") (name "Net-(U10-THERM)") (class "Default")
      (node (ref "R8") (pin "1") (pinfunction "1_1") (pintype "passive"))
      (node (ref "U10") (pin "8") (pinfunction "THERM_8") (pintype "bidirectional"))
    )
    (net (code "76") (name "POWER_BTN") (class "Default")
      (node (ref "C23") (pin "1") (pinfunction "1_1") (pintype "passive"))
      (node (ref "D4") (pin "C") (pinfunction "C_C") (pintype "passive"))
      (node (ref "J8") (pin "2") (pinfunction "2_2") (pintype "bidirectional"))
      (node (ref "R31") (pin "1") (pinfunction "1_1") (pintype "passive"))
    )
    (net (code "77") (name "USB_DM") (class "Default")
      (node (ref "J18") (pin "8") (pinfunction "8_8") (pintype "bidirectional"))
      (node (ref "R25") (pin "1") (pinfunction "1_1") (pintype "passive"))
    )
    (net (code "78") (name "USB_DP") (class "Default")
      (node (ref "J18") (pin "7") (pinfunction "7_7") (pintype "bidirectional"))
      (node (ref "R32") (pin "1") (pinfunction "1_1") (pintype "passive"))
    )
    (net (code "79") (name "VBUS_DET") (class "Default")
      (node (ref "C29") (pin "1") (pinfunction "1_1") (pintype "passive"))
      (node (ref "R19") (pin "2") (pinfunction "2_2") (pintype "passive"))
      (node (ref "R21") (pin "1") (pinfunction "1_1") (pintype "passive"))
      (node (ref "U8") (pin "27") (pinfunction "VBUS_DET_27") (pintype "bidirectional"))
    )
    (net (code "80") (name "VOUT") (class "Default")
      (node (ref "C20") (pin "1") (pinfunction "1_1") (pintype "passive"))
      (node (ref "C27") (pin "1") (pinfunction "1_1") (pintype "passive"))
      (node (ref "C6") (pin "1") (pinfunction "1_1") (pintype "passive"))
      (node (ref "Q3") (pin "D2") (pinfunction "D_D2") (pintype "bidirectional"))
      (node (ref "R22") (pin "2") (pinfunction "2_2") (pintype "passive"))
      (node (ref "U12") (pin "1") (pinfunction "IN_1") (pintype "input"))
      (node (ref "U2") (pin "1") (pinfunction "IN_1") (pintype "input"))
      (node (ref "U2") (pin "3") (pinfunction "EN_3") (pintype "input"))
    )
    (net (code "81") (name "V_BATT") (class "Default")
      (node (ref "C15") (pin "1") (pinfunction "1_1") (pintype "passive"))
      (node (ref "C17") (pin "1") (pinfunction "1_1") (pintype "passive"))
      (node (ref "C3") (pin "1") (pinfunction "1_1") (pintype "passive"))
      (node (ref "D7") (pin "A") (pinfunction "A_A") (pintype "passive"))
      (node (ref "J15") (pin "6") (pinfunction "6_6") (pintype "bidirectional"))
      (node (ref "J15") (pin "7") (pinfunction "7_7") (pintype "bidirectional"))
      (node (ref "J15") (pin "8") (pinfunction "8_8") (pintype "bidirectional"))
      (node (ref "J15") (pin "9") (pinfunction "9_9") (pintype "bidirectional"))
      (node (ref "MEAS2") (pin "2") (pinfunction "2_2") (pintype "passive"))
      (node (ref "MEAS2") (pin "4") (pinfunction "2_4") (pintype "passive"))
      (node (ref "U10") (pin "10") (pinfunction "VBAT_10") (pintype "bidirectional"))
      (node (ref "U10") (pin "9") (pinfunction "VBAT_9") (pintype "bidirectional"))
      (node (ref "U4") (pin "1") (pinfunction "IN_1") (pintype "input"))
      (node (ref "U4") (pin "3") (pinfunction "EN_3") (pintype "input"))
      (node (ref "U7") (pin "2") (pinfunction "CELL_2") (pintype "input"))
      (node (ref "U7") (pin "3") (pinfunction "VDD_3") (pintype "bidirectional"))
    )
    (net (code "82") (name "V_RAW") (class "Default")
      (node (ref "C16") (pin "1") (pinfunction "1_1") (pintype "passive"))
      (node (ref "C22") (pin "2") (pinfunction "2_2") (pintype "passive"))
      (node (ref "D2") (pin "C") (pinfunction "C_C") (pintype "passive"))
      (node (ref "D7") (pin "C") (pinfunction "C_C") (pintype "passive"))
      (node (ref "Q3") (pin "S2") (pinfunction "S_S2") (pintype "bidirectional"))
      (node (ref "R26") (pin "2") (pinfunction "2_2") (pintype "passive"))
      (node (ref "R31") (pin "2") (pinfunction "2_2") (pintype "passive"))
      (node (ref "U10") (pin "1") (pinfunction "VDD_1") (pintype "bidirectional"))
      (node (ref "U10") (pin "2") (pinfunction "VDD_2") (pintype "bidirectional"))
    )
    (net (code "83") (name "V_USB") (class "Default")
      (node (ref "D2") (pin "A") (pinfunction "A_A") (pintype "passive"))
      (node (ref "J15") (pin "1") (pinfunction "1_1") (pintype "bidirectional"))
      (node (ref "J15") (pin "2") (pinfunction "2_2") (pintype "bidirectional"))
      (node (ref "J15") (pin "3") (pinfunction "3_3") (pintype "bidirectional"))
      (node (ref "J15") (pin "4") (pinfunction "4_4") (pintype "bidirectional"))
      (node (ref "J8") (pin "12") (pinfunction "12_12") (pintype "bidirectional"))
      (node (ref "R21") (pin "2") (pinfunction "2_2") (pintype "passive"))
    )
    (net (code "84") (name "ZED-RXI2") (class "Default")
      (node (ref "J18") (pin "9") (pinfunction "9_9") (pintype "bidirectional"))
      (node (ref "R4") (pin "P3") (pinfunction "1_P3") (pintype "passive"))
    )
    (net (code "85") (name "ZED-TXO2") (class "Default")
      (node (ref "J18") (pin "10") (pinfunction "10_10") (pintype "bidirectional"))
      (node (ref "R4") (pin "P4") (pinfunction "1_P4") (pintype "passive"))
    )
    (net (code "86") (name "ZED_BACKUP") (class "Default")
      (node (ref "C18") (pin "1") (pinfunction "1_1") (pintype "passive"))
      (node (ref "U3") (pin "36") (pinfunction "V_BKCP_36") (pintype "bidirectional"))
      (node (ref "U4") (pin "5") (pinfunction "OUT_5") (pintype "passive"))
    )
    (net (code "87") (name "ZED_DM") (class "Default")
      (node (ref "R28") (pin "1") (pinfunction "1_1") (pintype "passive"))
      (node (ref "U8") (pin "1") (pinfunction "USBDM_DN1_1") (pintype "bidirectional"))
    )
    (net (code "88") (name "ZED_DP") (class "Default")
      (node (ref "R27") (pin "1") (pinfunction "1_1") (pintype "passive"))
      (node (ref "U8") (pin "2") (pinfunction "USBDP_DN1_2") (pintype "bidirectional"))
    )
    (net (code "89") (name "ZED_EXTINT") (class "Default")
      (node (ref "R2") (pin "P7") (pinfunction "2_P7") (pintype "passive"))
      (node (ref "U1") (pin "5") (pinfunction "Y1_5") (pintype "bidirectional"))
    )
    (net (code "90") (name "ZED_FENCE_STAT") (class "Default")
      (node (ref "R4") (pin "P1") (pinfunction "1_P1") (pintype "passive"))
    )
    (net (code "91") (name "ZED_PPS_STAT") (class "Default")
      (node (ref "J4") (pin "2") (pinfunction "2_2") (pintype "passive"))
      (node (ref "R2") (pin "P8") (pinfunction "2_P8") (pintype "passive"))
      (node (ref "U1") (pin "14") (pinfunction "X1_14") (pintype "bidirectional"))
    )
    (net (code "92") (name "ZED_RTK_STAT") (class "Default")
      (node (ref "R4") (pin "P2") (pinfunction "1_P2") (pintype "passive"))
    )
    (net (code "93") (name "ZED_~{SAFE}") (class "Default")
      (node (ref "R2") (pin "P6") (pinfunction "2_P6") (pintype "passive"))
    )
    (net (code "94") (name "unconnected-(J7-PAD1-PadNC1)") (class "Default")
      (node (ref "J7") (pin "NC1") (pinfunction "PAD1_NC1") (pintype "bidirectional"))
    )
    (net (code "95") (name "unconnected-(J7-PAD2-PadNC2)") (class "Default")
      (node (ref "J7") (pin "NC2") (pinfunction "PAD2_NC2") (pintype "bidirectional"))
    )
    (net (code "96") (name "unconnected-(J15-Pad5)") (class "Default")
      (node (ref "J15") (pin "5") (pinfunction "5_5") (pintype "bidirectional"))
    )
    (net (code "97") (name "unconnected-(U2-NC-Pad4)") (class "Default")
      (node (ref "U2") (pin "4") (pinfunction "NC_4") (pintype "no_connect"))
    )
    (net (code "98") (name "unconnected-(U3-ANT_DETECT-Pad4)") (class "Default")
      (node (ref "U3") (pin "4") (pinfunction "ANT_DETECT_4") (pintype "bidirectional"))
    )
    (net (code "99") (name "unconnected-(U3-ANT_OFF-Pad5)") (class "Default")
      (node (ref "U3") (pin "5") (pinfunction "ANT_OFF_5") (pintype "bidirectional"))
    )
    (net (code "100") (name "unconnected-(U3-D_SEL-Pad47)") (class "Default")
      (node (ref "U3") (pin "47") (pinfunction "D_SEL_47") (pintype "bidirectional"))
    )
    (net (code "101") (name "unconnected-(U3-~{ANT_SHORT}-Pad6)") (class "Default")
      (node (ref "U3") (pin "6") (pinfunction "~{ANT_SHORT}_6") (pintype "bidirectional"))
    )
    (net (code "102") (name "unconnected-(U4-NC-Pad4)") (class "Default")
      (node (ref "U4") (pin "4") (pinfunction "NC_4") (pintype "no_connect"))
    )
    (net (code "103") (name "unconnected-(U5-SCK{slash}IO6-Pad20)") (class "Default")
      (node (ref "U5") (pin "20") (pinfunction "SCK/IO6_20") (pintype "bidirectional"))
    )
    (net (code "104") (name "unconnected-(U5-SCS{slash}IO11-Pad19)") (class "Default")
      (node (ref "U5") (pin "19") (pinfunction "SCS/IO11_19") (pintype "bidirectional"))
    )
    (net (code "105") (name "unconnected-(U5-SDI{slash}IO8-Pad22)") (class "Default")
      (node (ref "U5") (pin "22") (pinfunction "SDI/IO8_22") (pintype "bidirectional"))
    )
    (net (code "106") (name "unconnected-(U5-SDO{slash}IO7-Pad21)") (class "Default")
      (node (ref "U5") (pin "21") (pinfunction "SDO/IO7_21") (pintype "bidirectional"))
    )
    (net (code "107") (name "unconnected-(U5-SHD{slash}IO9-Pad17)") (class "Default")
      (node (ref "U5") (pin "17") (pinfunction "SHD/IO9_17") (pintype "bidirectional"))
    )
    (net (code "108") (name "unconnected-(U5-SWP{slash}IO10-Pad18)") (class "Default")
      (node (ref "U5") (pin "18") (pinfunction "SWP/IO10_18") (pintype "bidirectional"))
    )
    (net (code "109") (name "unconnected-(U6-R232-Pad15)") (class "Default")
      (node (ref "U6") (pin "15") (pinfunction "R232_15") (pintype "bidirectional"))
    )
    (net (code "110") (name "unconnected-(U6-~{CTS}-Pad9)") (class "Default")
      (node (ref "U6") (pin "9") (pinfunction "~{CTS}_9") (pintype "bidirectional"))
    )
    (net (code "111") (name "unconnected-(U6-~{DCD}-Pad12)") (class "Default")
      (node (ref "U6") (pin "12") (pinfunction "~{DCD}_12") (pintype "bidirectional"))
    )
    (net (code "112") (name "unconnected-(U6-~{DSR}-Pad10)") (class "Default")
      (node (ref "U6") (pin "10") (pinfunction "~{DSR}_10") (pintype "bidirectional"))
    )
    (net (code "113") (name "unconnected-(U6-~{RI}-Pad11)") (class "Default")
      (node (ref "U6") (pin "11") (pinfunction "~{RI}_11") (pintype "bidirectional"))
    )
    (net (code "114") (name "unconnected-(U8-PRTPWR1-Pad12)") (class "Default")
      (node (ref "U8") (pin "12") (pinfunction "PRTPWR1_12") (pintype "bidirectional"))
    )
    (net (code "115") (name "unconnected-(U8-PRTPWR2-Pad16)") (class "Default")
      (node (ref "U8") (pin "16") (pinfunction "PRTPWR2_16") (pintype "bidirectional"))
    )
    (net (code "116") (name "unconnected-(U8-PRTPWR3-Pad18)") (class "Default")
      (node (ref "U8") (pin "18") (pinfunction "PRTPWR3_18") (pintype "bidirectional"))
    )
    (net (code "117") (name "unconnected-(U8-PRTPWR4-Pad20)") (class "Default")
      (node (ref "U8") (pin "20") (pinfunction "PRTPWR4_20") (pintype "bidirectional"))
    )
    (net (code "118") (name "unconnected-(U8-USBDM_DN3-Pad6)") (class "Default")
      (node (ref "U8") (pin "6") (pinfunction "USBDM_DN3_6") (pintype "bidirectional"))
    )
    (net (code "119") (name "unconnected-(U8-USBDM_DN4-Pad8)") (class "Default")
      (node (ref "U8") (pin "8") (pinfunction "USBDM_DN4_8") (pintype "bidirectional"))
    )
    (net (code "120") (name "unconnected-(U8-USBDP_DN3-Pad7)") (class "Default")
      (node (ref "U8") (pin "7") (pinfunction "USBDP_DN3_7") (pintype "bidirectional"))
    )
    (net (code "121") (name "unconnected-(U8-USBDP_DN4-Pad9)") (class "Default")
      (node (ref "U8") (pin "9") (pinfunction "USBDP_DN4_9") (pintype "bidirectional"))
    )
    (net (code "122") (name "unconnected-(U8-~{OCS1}-Pad13)") (class "Default")
      (node (ref "U8") (pin "13") (pinfunction "~{OCS1}_13") (pintype "bidirectional"))
    )
    (net (code "123") (name "unconnected-(U8-~{OCS2}-Pad17)") (class "Default")
      (node (ref "U8") (pin "17") (pinfunction "~{OCS2}_17") (pintype "bidirectional"))
    )
    (net (code "124") (name "unconnected-(U8-~{OCS3}-Pad19)") (class "Default")
      (node (ref "U8") (pin "19") (pinfunction "~{OCS3}_19") (pintype "bidirectional"))
    )
    (net (code "125") (name "unconnected-(U8-~{OCS4}-Pad21)") (class "Default")
      (node (ref "U8") (pin "21") (pinfunction "~{OCS4}_21") (pintype "bidirectional"))
    )
    (net (code "126") (name "unconnected-(U10-STAT2-Pad4)") (class "Default")
      (node (ref "U10") (pin "4") (pinfunction "STAT2_4") (pintype "bidirectional"))
    )
    (net (code "127") (name "unconnected-(U10-~{PG}-Pad7)") (class "Default")
      (node (ref "U10") (pin "7") (pinfunction "~{PG}_7") (pintype "bidirectional"))
    )
    (net (code "128") (name "unconnected-(U12-NC-Pad4)") (class "Default")
      (node (ref "U12") (pin "4") (pinfunction "NC_4") (pintype "no_connect"))
    )
  )
)
